# BP_Header.net
KiCad netlist of a schematic drawn in Altium Designer
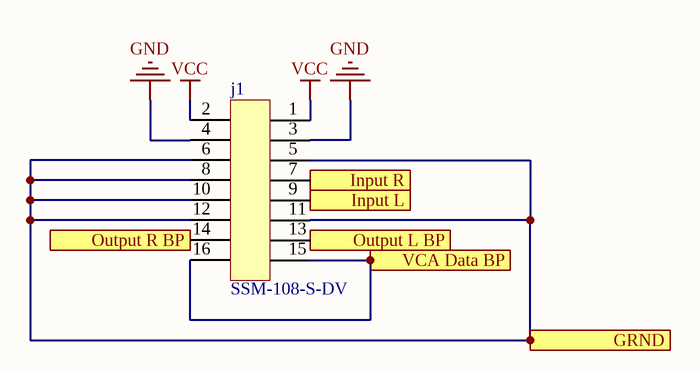
[diagram p0: BP Header.SchDoc]

(export (version "E")
  (design (tool "Eeschema 10.0.6"))
  (components
    (comp (ref "j1")
      (value "SSM-108-S-DV")
      (footprint "Band Pass Board")
      (libsource (lib "Schlib") (part "Band Pass Board"))
    )
  )
  (nets
    (net (code "1") (name "/GRND") (class "Default")
      (node (ref "j1") (pin "10") (pinfunction "K_10") (pintype "passive"))
      (node (ref "j1") (pin "11") (pinfunction "K_11") (pintype "passive"))
      (node (ref "j1") (pin "12") (pinfunction "K_12") (pintype "passive"))
      (node (ref "j1") (pin "5") (pinfunction "K_5") (pintype "passive"))
      (node (ref "j1") (pin "6") (pinfunction "K_6") (pintype "passive"))
      (node (ref "j1") (pin "8") (pinfunction "K_8") (pintype "passive"))
    )
    (net (code "2") (name "/Input L") (class "Default")
      (node (ref "j1") (pin "9") (pinfunction "K_9") (pintype "passive"))
    )
    (net (code "3") (name "/Input R") (class "Default")
      (node (ref "j1") (pin "7") (pinfunction "K_7") (pintype "passive"))
    )
    (net (code "4") (name "/Output L BP") (class "Default")
      (node (ref "j1") (pin "13") (pinfunction "K_13") (pintype "passive"))
    )
    (net (code "5") (name "/Output R BP") (class "Default")
      (node (ref "j1") (pin "14") (pinfunction "K_14") (pintype "passive"))
    )
    (net (code "6") (name "/VCA Data BP") (class "Default")
      (node (ref "j1") (pin "15") (pinfunction "15_15") (pintype "passive"))
      (node (ref "j1") (pin "16") (pinfunction "16_16") (pintype "passive"))
    )
    (net (code "7") (name "GND") (class "Default")
      (node (ref "j1") (pin "3") (pinfunction "K_3") (pintype "passive"))
      (node (ref "j1") (pin "4") (pinfunction "K_4") (pintype "passive"))
    )
    (net (code "8") (name "VCC") (class "Default")
      (node (ref "j1") (pin "1") (pinfunction "K_1") (pintype "passive"))
      (node (ref "j1") (pin "2") (pinfunction "K_2") (pintype "passive"))
    )
  )
)
